# RaspberryPi.net
KiCad netlist of a schematic drawn in Altium Designer
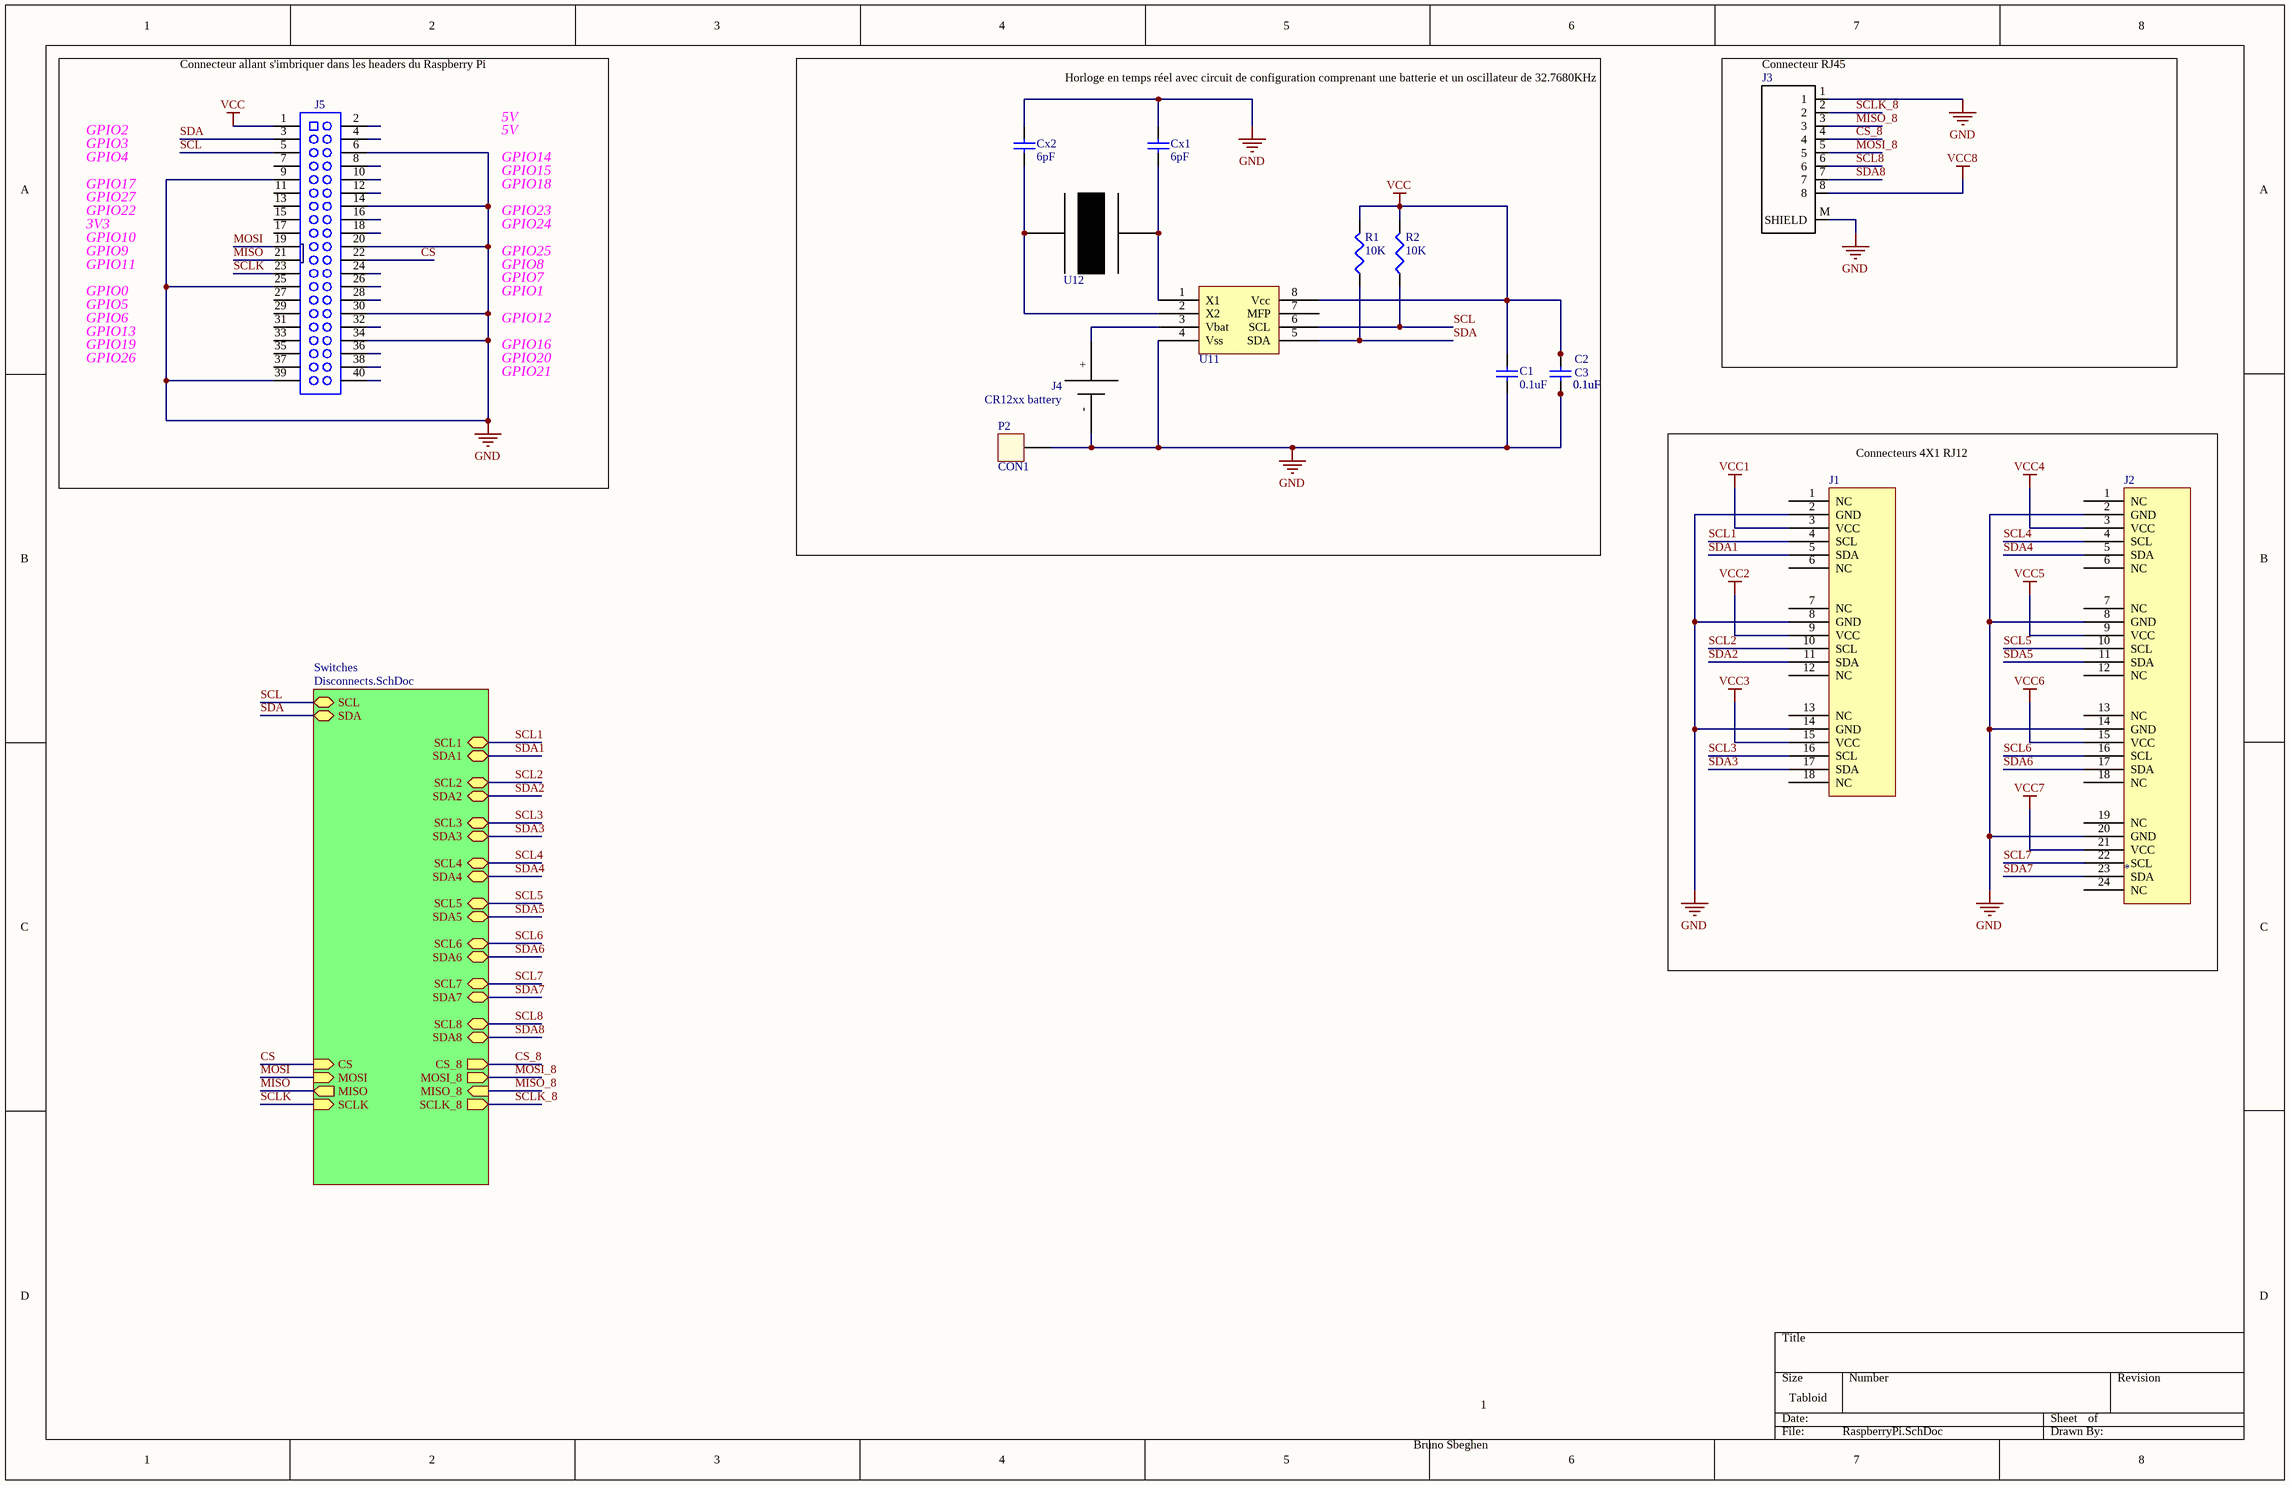
[diagram p0: RaspberryPi.SchDoc]

(export (version "E")
  (design (tool "Eeschema 10.0.6"))
  (components
    (comp (ref "C1")
      (value "0.1uF")
      (footprint "C0805")
      (description "Capacitor 0.1uF")
      (fields (field (name "Comment") "Cap 0.1uF") (field (name "PUBLISHER") "Altium Limited"))
      (libsource (lib "MOvIT-Detect PCB") (part "Cap 0.1uF"))
    )
    (comp (ref "C2")
      (value "0.1uF")
      (footprint "C0805")
      (description "Capacitor 0.1uF")
      (fields (field (name "Comment") "Cap 0.1uF") (field (name "PUBLISHER") "Altium Limited"))
      (libsource (lib "MOvIT-Detect PCB") (part "Cap 0.1uF"))
    )
    (comp (ref "C3")
      (value "0.1uF")
      (footprint "C0805")
      (description "Capacitor 0.1uF")
      (fields (field (name "Comment") "Cap 0.1uF") (field (name "PUBLISHER") "Altium Limited"))
      (libsource (lib "MOvIT-Detect PCB") (part "Cap 0.1uF"))
    )
    (comp (ref "Cx1")
      (value "6pF")
      (footprint "C0805")
      (description "Capacitor 6pF")
      (fields (field (name "Comment") "Cap 6pF") (field (name "PUBLISHER") "Altium Limited"))
      (libsource (lib "MOvIT-Detect PCB") (part "Cap 6pF"))
    )
    (comp (ref "Cx2")
      (value "6pF")
      (footprint "C0805")
      (description "Capacitor 6pF")
      (fields (field (name "Comment") "Cap 6pF") (field (name "PUBLISHER") "Altium Limited"))
      (libsource (lib "MOvIT-Detect PCB") (part "Cap 6pF"))
    )
    (comp (ref "J1")
      (value "TM2RE-1818(50)")
      (footprint "TM2RE-1818")
      (description "Connector MOD JACK 3pos")
      (libsource (lib "MOvIT-Detect PCB") (part "TM2RE-1818(50)"))
    )
    (comp (ref "J2")
      (value "*")
      (footprint "TM2RE-2424")
      (description "Connector MOD JACK 4pos")
      (libsource (lib "MOvIT-Detect PCB") (part "TM2RE-2424(50)"))
    )
    (comp (ref "J3")
      (value "TM3RA-88(50)")
      (footprint "TM3RA-88(50)")
      (description "Signal Line; Modular; 8 Contacts; 1 Port Through Hole Vertical")
      (fields (field (name "MF") "Hirose"))
      (libsource (lib "MOvIT-Detect PCB") (part "TM3RA-88(50)"))
    )
    (comp (ref "J4")
      (value "CR12xx battery")
      (footprint "BS-1225-PC")
      (description "12mm Battery holder")
      (libsource (lib "MOvIT-Detect PCB") (part "CONN_BATT_12mm_VERTICAL"))
    )
    (comp (ref "J5")
      (value "??")
      (footprint "CONN40_100mils_M20_7812045")
      (description "IDC Boxed Header, Straight, PCB Mount, Polarised, 40 Way, 2x20, 0.1\" Pitch")
      (fields (field (name "MFG") "Harwin"))
      (libsource (lib "INTER_2014") (part "CON40_2x20"))
    )
    (comp (ref "P2")
      (value "CON1")
      (footprint "CONN1_100mils")
      (description "TP")
      (libsource (lib "INTER_2014") (part "CON1"))
    )
    (comp (ref "R1")
      (value "10K")
      (footprint "6-0805_N")
      (description "Resistor 10K")
      (fields (field (name "Comment") "Res 10K") (field (name "PUBLISHER") "Altium Limited"))
      (libsource (lib "MOvIT-Detect PCB") (part "Res 10K"))
    )
    (comp (ref "R2")
      (value "10K")
      (footprint "6-0805_N")
      (description "Resistor 10K")
      (fields (field (name "Comment") "Res 10K") (field (name "PUBLISHER") "Altium Limited"))
      (libsource (lib "MOvIT-Detect PCB") (part "Res 10K"))
    )
    (comp (ref "U11")
      (value "*")
      (footprint "MCP79410")
      (description "RTC")
      (libsource (lib "MOvIT-Detect PCB") (part "MCP79410"))
    )
    (comp (ref "U12")
      (value "*")
      (footprint "ECX-31B")
      (description "Oscillator 32.7680KHz")
      (libsource (lib "MOvIT-Detect PCB") (part "AB38T"))
    )
  )
  (nets
    (net (code "2") (name "/CS") (class "Default")
      (node (ref "J5") (pin "22") (pinfunction "22_22") (pintype "passive"))
    )
    (net (code "3") (name "/CS_8") (class "Default")
      (node (ref "J3") (pin "4") (pinfunction "4_4") (pintype "passive"))
    )
    (net (code "4") (name "/MISO") (class "Default")
      (node (ref "J5") (pin "21") (pinfunction "21_21") (pintype "passive"))
    )
    (net (code "5") (name "/MISO_8") (class "Default")
      (node (ref "J3") (pin "3") (pinfunction "3_3") (pintype "passive"))
    )
    (net (code "6") (name "/MOSI") (class "Default")
      (node (ref "J5") (pin "19") (pinfunction "19_19") (pintype "passive"))
    )
    (net (code "7") (name "/MOSI_8") (class "Default")
      (node (ref "J3") (pin "5") (pinfunction "5_5") (pintype "passive"))
    )
    (net (code "8") (name "/SCL") (class "Default")
      (node (ref "J5") (pin "5") (pinfunction "5_5") (pintype "passive"))
      (node (ref "R2") (pin "1") (pinfunction "1_1") (pintype "passive"))
      (node (ref "U11") (pin "6") (pinfunction "SCL_6") (pintype "passive"))
    )
    (net (code "9") (name "/SCL1") (class "Default")
      (node (ref "J1") (pin "4") (pinfunction "SCL_4") (pintype "passive"))
    )
    (net (code "10") (name "/SCL2") (class "Default")
      (node (ref "J1") (pin "10") (pinfunction "SCL_10") (pintype "passive"))
    )
    (net (code "11") (name "/SCL3") (class "Default")
      (node (ref "J1") (pin "16") (pinfunction "SCL_16") (pintype "passive"))
    )
    (net (code "12") (name "/SCL4") (class "Default")
      (node (ref "J2") (pin "4") (pinfunction "SCL_4") (pintype "passive"))
    )
    (net (code "13") (name "/SCL5") (class "Default")
      (node (ref "J2") (pin "10") (pinfunction "SCL_10") (pintype "passive"))
    )
    (net (code "14") (name "/SCL6") (class "Default")
      (node (ref "J2") (pin "16") (pinfunction "SCL_16") (pintype "passive"))
    )
    (net (code "15") (name "/SCL7") (class "Default")
      (node (ref "J2") (pin "22") (pinfunction "SCL_22") (pintype "passive"))
    )
    (net (code "16") (name "/SCL8") (class "Default")
      (node (ref "J3") (pin "6") (pinfunction "6_6") (pintype "passive"))
    )
    (net (code "17") (name "/SCLK") (class "Default")
      (node (ref "J5") (pin "23") (pinfunction "23_23") (pintype "passive"))
    )
    (net (code "18") (name "/SCLK_8") (class "Default")
      (node (ref "J3") (pin "2") (pinfunction "2_2") (pintype "passive"))
    )
    (net (code "19") (name "/SDA") (class "Default")
      (node (ref "J5") (pin "3") (pinfunction "3_3") (pintype "passive"))
      (node (ref "R1") (pin "1") (pinfunction "1_1") (pintype "passive"))
      (node (ref "U11") (pin "5") (pinfunction "SDA_5") (pintype "passive"))
    )
    (net (code "20") (name "/SDA1") (class "Default")
      (node (ref "J1") (pin "5") (pinfunction "SDA_5") (pintype "passive"))
    )
    (net (code "21") (name "/SDA2") (class "Default")
      (node (ref "J1") (pin "11") (pinfunction "SDA_11") (pintype "passive"))
    )
    (net (code "22") (name "/SDA3") (class "Default")
      (node (ref "J1") (pin "17") (pinfunction "SDA_17") (pintype "passive"))
    )
    (net (code "23") (name "/SDA4") (class "Default")
      (node (ref "J2") (pin "5") (pinfunction "SDA_5") (pintype "passive"))
    )
    (net (code "24") (name "/SDA5") (class "Default")
      (node (ref "J2") (pin "11") (pinfunction "SDA_11") (pintype "passive"))
    )
    (net (code "25") (name "/SDA6") (class "Default")
      (node (ref "J2") (pin "17") (pinfunction "SDA_17") (pintype "passive"))
    )
    (net (code "26") (name "/SDA7") (class "Default")
      (node (ref "J2") (pin "23") (pinfunction "SDA_23") (pintype "passive"))
    )
    (net (code "27") (name "/SDA8") (class "Default")
      (node (ref "J3") (pin "7") (pinfunction "7_7") (pintype "passive"))
    )
    (net (code "28") (name "GND") (class "Default")
      (node (ref "C1") (pin "1") (pinfunction "1_1") (pintype "passive"))
      (node (ref "C2") (pin "1") (pinfunction "1_1") (pintype "passive"))
      (node (ref "C3") (pin "1") (pinfunction "1_1") (pintype "passive"))
      (node (ref "Cx1") (pin "2") (pinfunction "2_2") (pintype "passive"))
      (node (ref "Cx2") (pin "2") (pinfunction "2_2") (pintype "passive"))
      (node (ref "J1") (pin "14") (pinfunction "GND_14") (pintype "passive"))
      (node (ref "J1") (pin "2") (pinfunction "GND_2") (pintype "passive"))
      (node (ref "J1") (pin "8") (pinfunction "GND_8") (pintype "passive"))
      (node (ref "J2") (pin "14") (pinfunction "GND_14") (pintype "passive"))
      (node (ref "J2") (pin "2") (pinfunction "GND_2") (pintype "passive"))
      (node (ref "J2") (pin "20") (pinfunction "GND_20") (pintype "passive"))
      (node (ref "J2") (pin "8") (pinfunction "GND_8") (pintype "passive"))
      (node (ref "J3") (pin "1") (pinfunction "1_1") (pintype "passive"))
      (node (ref "J3") (pin "M") (pinfunction "SHIELD_M") (pintype "passive"))
      (node (ref "J4") (pin "-") (pintype "passive"))
      (node (ref "J5") (pin "14") (pinfunction "14_14") (pintype "passive"))
      (node (ref "J5") (pin "20") (pinfunction "20_20") (pintype "passive"))
      (node (ref "J5") (pin "25") (pinfunction "25_25") (pintype "passive"))
      (node (ref "J5") (pin "30") (pinfunction "30_30") (pintype "passive"))
      (node (ref "J5") (pin "34") (pinfunction "34_34") (pintype "passive"))
      (node (ref "J5") (pin "39") (pinfunction "39_39") (pintype "passive"))
      (node (ref "J5") (pin "6") (pinfunction "6_6") (pintype "passive"))
      (node (ref "J5") (pin "9") (pinfunction "9_9") (pintype "passive"))
      (node (ref "P2") (pin "1") (pintype "passive"))
      (node (ref "U11") (pin "4") (pinfunction "Vss_4") (pintype "passive"))
    )
    (net (code "29") (name "Net-(U11-Vbat)") (class "Default")
      (node (ref "J4") (pin "+") (pintype "passive"))
      (node (ref "U11") (pin "3") (pinfunction "Vbat_3") (pintype "passive"))
    )
    (net (code "30") (name "Net-(U11-X1)") (class "Default")
      (node (ref "Cx1") (pin "1") (pinfunction "1_1") (pintype "passive"))
      (node (ref "U11") (pin "1") (pinfunction "X1_1") (pintype "passive"))
      (node (ref "U12") (pin "2") (pintype "passive"))
    )
    (net (code "31") (name "Net-(U11-X2)") (class "Default")
      (node (ref "Cx2") (pin "1") (pinfunction "1_1") (pintype "passive"))
      (node (ref "U11") (pin "2") (pinfunction "X2_2") (pintype "passive"))
      (node (ref "U12") (pin "1") (pintype "passive"))
    )
    (net (code "32") (name "VCC") (class "Default")
      (node (ref "C1") (pin "2") (pinfunction "2_2") (pintype "passive"))
      (node (ref "C2") (pin "2") (pinfunction "2_2") (pintype "passive"))
      (node (ref "C3") (pin "2") (pinfunction "2_2") (pintype "passive"))
      (node (ref "J5") (pin "1") (pinfunction "1_1") (pintype "passive"))
      (node (ref "R1") (pin "2") (pinfunction "2_2") (pintype "passive"))
      (node (ref "R2") (pin "2") (pinfunction "2_2") (pintype "passive"))
      (node (ref "U11") (pin "8") (pinfunction "Vcc_8") (pintype "passive"))
    )
    (net (code "33") (name "VCC1") (class "Default")
      (node (ref "J1") (pin "3") (pinfunction "VCC_3") (pintype "passive"))
    )
    (net (code "34") (name "VCC2") (class "Default")
      (node (ref "J1") (pin "9") (pinfunction "VCC_9") (pintype "passive"))
    )
    (net (code "35") (name "VCC3") (class "Default")
      (node (ref "J1") (pin "15") (pinfunction "VCC_15") (pintype "passive"))
    )
    (net (code "36") (name "VCC4") (class "Default")
      (node (ref "J2") (pin "3") (pinfunction "VCC_3") (pintype "passive"))
    )
    (net (code "37") (name "VCC5") (class "Default")
      (node (ref "J2") (pin "9") (pinfunction "VCC_9") (pintype "passive"))
    )
    (net (code "38") (name "VCC6") (class "Default")
      (node (ref "J2") (pin "15") (pinfunction "VCC_15") (pintype "passive"))
    )
    (net (code "39") (name "VCC7") (class "Default")
      (node (ref "J2") (pin "21") (pinfunction "VCC_21") (pintype "passive"))
    )
    (net (code "40") (name "VCC8") (class "Default")
      (node (ref "J3") (pin "8") (pinfunction "8_8") (pintype "passive"))
    )
    (net (code "41") (name "unconnected-(J1-NC-Pad1)") (class "Default")
      (node (ref "J1") (pin "1") (pinfunction "NC_1") (pintype "passive"))
    )
    (net (code "42") (name "unconnected-(J1-NC-Pad6)") (class "Default")
      (node (ref "J1") (pin "6") (pinfunction "NC_6") (pintype "passive"))
    )
    (net (code "43") (name "unconnected-(J1-NC-Pad7)") (class "Default")
      (node (ref "J1") (pin "7") (pinfunction "NC_7") (pintype "passive"))
    )
    (net (code "44") (name "unconnected-(J1-NC-Pad12)") (class "Default")
      (node (ref "J1") (pin "12") (pinfunction "NC_12") (pintype "passive"))
    )
    (net (code "45") (name "unconnected-(J1-NC-Pad13)") (class "Default")
      (node (ref "J1") (pin "13") (pinfunction "NC_13") (pintype "passive"))
    )
    (net (code "46") (name "unconnected-(J1-NC-Pad18)") (class "Default")
      (node (ref "J1") (pin "18") (pinfunction "NC_18") (pintype "passive"))
    )
    (net (code "47") (name "unconnected-(J2-NC-Pad1)") (class "Default")
      (node (ref "J2") (pin "1") (pinfunction "NC_1") (pintype "passive"))
    )
    (net (code "48") (name "unconnected-(J2-NC-Pad6)") (class "Default")
      (node (ref "J2") (pin "6") (pinfunction "NC_6") (pintype "passive"))
    )
    (net (code "49") (name "unconnected-(J2-NC-Pad7)") (class "Default")
      (node (ref "J2") (pin "7") (pinfunction "NC_7") (pintype "passive"))
    )
    (net (code "50") (name "unconnected-(J2-NC-Pad12)") (class "Default")
      (node (ref "J2") (pin "12") (pinfunction "NC_12") (pintype "passive"))
    )
    (net (code "51") (name "unconnected-(J2-NC-Pad13)") (class "Default")
      (node (ref "J2") (pin "13") (pinfunction "NC_13") (pintype "passive"))
    )
    (net (code "52") (name "unconnected-(J2-NC-Pad18)") (class "Default")
      (node (ref "J2") (pin "18") (pinfunction "NC_18") (pintype "passive"))
    )
    (net (code "53") (name "unconnected-(J2-NC-Pad19)") (class "Default")
      (node (ref "J2") (pin "19") (pinfunction "NC_19") (pintype "passive"))
    )
    (net (code "54") (name "unconnected-(J2-NC-Pad24)") (class "Default")
      (node (ref "J2") (pin "24") (pinfunction "NC_24") (pintype "passive"))
    )
    (net (code "55") (name "unconnected-(J5-Pad2)") (class "Default")
      (node (ref "J5") (pin "2") (pinfunction "2_2") (pintype "passive"))
    )
    (net (code "56") (name "unconnected-(J5-Pad4)") (class "Default")
      (node (ref "J5") (pin "4") (pinfunction "4_4") (pintype "passive"))
    )
    (net (code "57") (name "unconnected-(J5-Pad7)") (class "Default")
      (node (ref "J5") (pin "7") (pinfunction "7_7") (pintype "passive"))
    )
    (net (code "58") (name "unconnected-(J5-Pad8)") (class "Default")
      (node (ref "J5") (pin "8") (pinfunction "8_8") (pintype "passive"))
    )
    (net (code "59") (name "unconnected-(J5-Pad10)") (class "Default")
      (node (ref "J5") (pin "10") (pinfunction "10_10") (pintype "passive"))
    )
    (net (code "60") (name "unconnected-(J5-Pad11)") (class "Default")
      (node (ref "J5") (pin "11") (pinfunction "11_11") (pintype "passive"))
    )
    (net (code "61") (name "unconnected-(J5-Pad12)") (class "Default")
      (node (ref "J5") (pin "12") (pinfunction "12_12") (pintype "passive"))
    )
    (net (code "62") (name "unconnected-(J5-Pad13)") (class "Default")
      (node (ref "J5") (pin "13") (pinfunction "13_13") (pintype "passive"))
    )
    (net (code "63") (name "unconnected-(J5-Pad15)") (class "Default")
      (node (ref "J5") (pin "15") (pinfunction "15_15") (pintype "passive"))
    )
    (net (code "64") (name "unconnected-(J5-Pad16)") (class "Default")
      (node (ref "J5") (pin "16") (pinfunction "16_16") (pintype "passive"))
    )
    (net (code "65") (name "unconnected-(J5-Pad17)") (class "Default")
      (node (ref "J5") (pin "17") (pinfunction "17_17") (pintype "passive"))
    )
    (net (code "66") (name "unconnected-(J5-Pad18)") (class "Default")
      (node (ref "J5") (pin "18") (pinfunction "18_18") (pintype "passive"))
    )
    (net (code "67") (name "unconnected-(J5-Pad24)") (class "Default")
      (node (ref "J5") (pin "24") (pinfunction "24_24") (pintype "passive"))
    )
    (net (code "68") (name "unconnected-(J5-Pad26)") (class "Default")
      (node (ref "J5") (pin "26") (pinfunction "26_26") (pintype "passive"))
    )
    (net (code "69") (name "unconnected-(J5-Pad27)") (class "Default")
      (node (ref "J5") (pin "27") (pinfunction "27_27") (pintype "passive"))
    )
    (net (code "70") (name "unconnected-(J5-Pad28)") (class "Default")
      (node (ref "J5") (pin "28") (pinfunction "28_28") (pintype "passive"))
    )
    (net (code "71") (name "unconnected-(J5-Pad29)") (class "Default")
      (node (ref "J5") (pin "29") (pinfunction "29_29") (pintype "passive"))
    )
    (net (code "72") (name "unconnected-(J5-Pad31)") (class "Default")
      (node (ref "J5") (pin "31") (pinfunction "31_31") (pintype "passive"))
    )
    (net (code "73") (name "unconnected-(J5-Pad32)") (class "Default")
      (node (ref "J5") (pin "32") (pinfunction "32_32") (pintype "passive"))
    )
    (net (code "74") (name "unconnected-(J5-Pad33)") (class "Default")
      (node (ref "J5") (pin "33") (pinfunction "33_33") (pintype "passive"))
    )
    (net (code "75") (name "unconnected-(J5-Pad35)") (class "Default")
      (node (ref "J5") (pin "35") (pinfunction "35_35") (pintype "passive"))
    )
    (net (code "76") (name "unconnected-(J5-Pad36)") (class "Default")
      (node (ref "J5") (pin "36") (pinfunction "36_36") (pintype "passive"))
    )
    (net (code "77") (name "unconnected-(J5-Pad37)") (class "Default")
      (node (ref "J5") (pin "37") (pinfunction "37_37") (pintype "passive"))
    )
    (net (code "78") (name "unconnected-(J5-Pad38)") (class "Default")
      (node (ref "J5") (pin "38") (pinfunction "38_38") (pintype "passive"))
    )
    (net (code "79") (name "unconnected-(J5-Pad40)") (class "Default")
      (node (ref "J5") (pin "40") (pinfunction "40_40") (pintype "passive"))
    )
    (net (code "80") (name "unconnected-(U11-MFP-Pad7)") (class "Default")
      (node (ref "U11") (pin "7") (pinfunction "MFP_7") (pintype "passive"))
    )
  )
)
